# LED_individual_sign_Board1.net
KiCad netlist of a schematic drawn in EAGLE
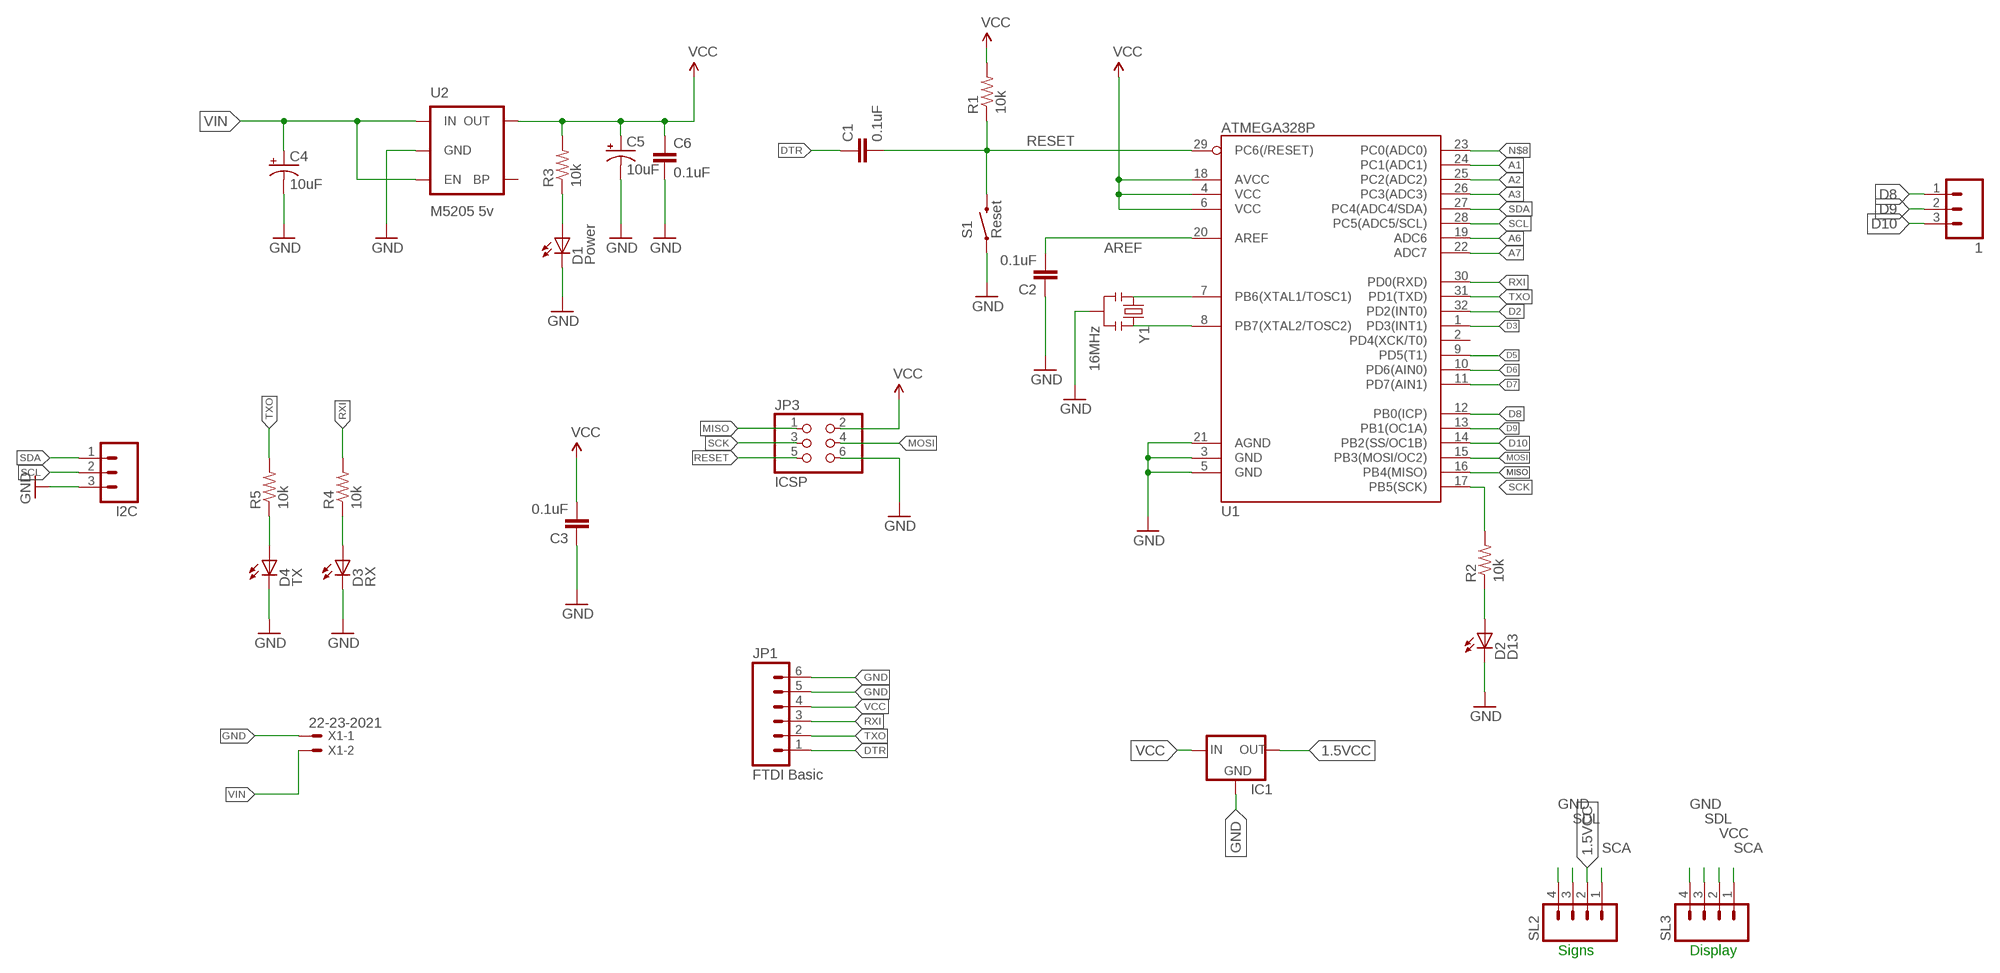
[diagram p0: schematic, sheet 1]

(export (version "E")
  (design (tool "Eeschema 10.0.6"))
  (components
    (comp (ref "1")
      (value "M03PTH")
      (footprint "eagle-import:1X03")
      (libsource (lib "eagle-import") (part "M03PTH"))
    )
    (comp (ref "C1")
      (value "0.1uF")
      (footprint "eagle-import:0603-CAP")
      (libsource (lib "eagle-import") (part "CAP0603-CAP"))
    )
    (comp (ref "C2")
      (value "0.1uF")
      (footprint "eagle-import:0603-CAP")
      (libsource (lib "eagle-import") (part "CAP0603-CAP"))
    )
    (comp (ref "C3")
      (value "0.1uF")
      (footprint "eagle-import:0603-CAP")
      (libsource (lib "eagle-import") (part "CAP0603-CAP"))
    )
    (comp (ref "C4")
      (value "10uF")
      (footprint "eagle-import:EIA3216")
      (libsource (lib "eagle-import") (part "CAP_POL1206"))
    )
    (comp (ref "C5")
      (value "10uF")
      (footprint "eagle-import:EIA3216")
      (libsource (lib "eagle-import") (part "CAP_POL1206"))
    )
    (comp (ref "C6")
      (value "0.1uF")
      (footprint "eagle-import:0603-CAP")
      (libsource (lib "eagle-import") (part "CAP0603-CAP"))
    )
    (comp (ref "D1")
      (value "Power")
      (footprint "eagle-import:LED-0603")
      (libsource (lib "eagle-import") (part "LED-RED0603"))
    )
    (comp (ref "D2")
      (value "D13")
      (footprint "eagle-import:LED-0603")
      (libsource (lib "eagle-import") (part "LED-RED0603"))
    )
    (comp (ref "D3")
      (value "RX")
      (footprint "eagle-import:LED-0603")
      (libsource (lib "eagle-import") (part "LED-GREEN0603"))
    )
    (comp (ref "D4")
      (value "TX")
      (footprint "eagle-import:LED-0603")
      (libsource (lib "eagle-import") (part "LED-RED0603"))
    )
    (comp (ref "I2C")
      (value "M03PTH")
      (footprint "eagle-import:1X03")
      (libsource (lib "eagle-import") (part "M03PTH"))
    )
    (comp (ref "IC1")
      (value "78XXS")
      (footprint "eagle-import:78XXS")
      (libsource (lib "eagle-import") (part "78XXS"))
    )
    (comp (ref "JP1")
      (value "FTDI Basic")
      (footprint "eagle-import:1X06")
      (libsource (lib "eagle-import") (part "M06SIP"))
    )
    (comp (ref "JP3")
      (value "ICSP")
      (footprint "eagle-import:2X03")
      (libsource (lib "eagle-import") (part "PINHD-2X3"))
    )
    (comp (ref "R1")
      (value "10k")
      (footprint "eagle-import:0603-RES")
      (libsource (lib "eagle-import") (part "RESISTOR0603-RES"))
    )
    (comp (ref "R2")
      (value "10k")
      (footprint "eagle-import:0603-RES")
      (libsource (lib "eagle-import") (part "RESISTOR0603-RES"))
    )
    (comp (ref "R3")
      (value "10k")
      (footprint "eagle-import:0603-RES")
      (libsource (lib "eagle-import") (part "RESISTOR0603-RES"))
    )
    (comp (ref "R4")
      (value "10k")
      (footprint "eagle-import:0603-RES")
      (libsource (lib "eagle-import") (part "RESISTOR0603-RES"))
    )
    (comp (ref "R5")
      (value "10k")
      (footprint "eagle-import:0603-RES")
      (libsource (lib "eagle-import") (part "RESISTOR0603-RES"))
    )
    (comp (ref "S1")
      (value "Reset")
      (footprint "eagle-import:TACTILE_SWITCH_SMD")
      (libsource (lib "eagle-import") (part "SWITCH-MOMENTARY-2SMD"))
    )
    (comp (ref "SL2")
      (value "M04")
      (footprint "eagle-import:04P")
      (libsource (lib "eagle-import") (part "M04"))
    )
    (comp (ref "SL3")
      (value "M04")
      (footprint "eagle-import:04P")
      (libsource (lib "eagle-import") (part "M04"))
    )
    (comp (ref "U1")
      (value "ATMEGA328P")
      (footprint "eagle-import:TQFP32-08")
      (libsource (lib "eagle-import") (part "ATMEGA328_SMT"))
    )
    (comp (ref "U2")
      (value "M5205 5v")
      (footprint "eagle-import:SOT23-5")
      (libsource (lib "eagle-import") (part "MIC52055V"))
    )
    (comp (ref "X1")
      (value "22-23-2021")
      (footprint "eagle-import:22-23-2021")
      (fields (field (name "MF") "MOLEX"))
      (libsource (lib "eagle-import") (part "22-23-2021"))
    )
    (comp (ref "Y1")
      (value "16MHz")
      (footprint "eagle-import:RESONATOR-SMD")
      (libsource (lib "eagle-import") (part "RESONATOR16MHZ"))
    )
  )
  (nets
    (net (code "1") (name "/AREF") (class "Default")
      (node (ref "C2") (pin "2") (pinfunction "2_2") (pintype "passive"))
      (node (ref "U1") (pin "20") (pinfunction "AREF_20") (pintype "bidirectional"))
    )
    (net (code "2") (name "/SCA") (class "Default")
      (node (ref "SL2") (pin "1") (pinfunction "1_1") (pintype "passive"))
      (node (ref "SL3") (pin "1") (pinfunction "1_1") (pintype "passive"))
    )
    (net (code "3") (name "/SDL") (class "Default")
      (node (ref "SL2") (pin "3") (pinfunction "3_3") (pintype "passive"))
      (node (ref "SL3") (pin "3") (pinfunction "3_3") (pintype "passive"))
    )
    (net (code "4") (name "1.5VCC") (class "Default")
      (node (ref "IC1") (pin "OUT") (pinfunction "OUT_OUT") (pintype "passive"))
      (node (ref "SL2") (pin "2") (pinfunction "2_2") (pintype "passive"))
    )
    (net (code "5") (name "A1") (class "Default")
      (node (ref "U1") (pin "24") (pinfunction "PC1(ADC1)_24") (pintype "bidirectional"))
    )
    (net (code "6") (name "A2") (class "Default")
      (node (ref "U1") (pin "25") (pinfunction "PC2(ADC2)_25") (pintype "bidirectional"))
    )
    (net (code "7") (name "A3") (class "Default")
      (node (ref "U1") (pin "26") (pinfunction "PC3(ADC3)_26") (pintype "bidirectional"))
    )
    (net (code "8") (name "A6") (class "Default")
      (node (ref "U1") (pin "19") (pinfunction "ADC6_19") (pintype "bidirectional"))
    )
    (net (code "9") (name "A7") (class "Default")
      (node (ref "U1") (pin "22") (pinfunction "ADC7_22") (pintype "bidirectional"))
    )
    (net (code "10") (name "D2") (class "Default")
      (node (ref "U1") (pin "32") (pinfunction "PD2(INT0)_32") (pintype "bidirectional"))
    )
    (net (code "11") (name "D3") (class "Default")
      (node (ref "U1") (pin "1") (pinfunction "PD3(INT1)_1") (pintype "bidirectional"))
    )
    (net (code "12") (name "D5") (class "Default")
      (node (ref "U1") (pin "9") (pinfunction "PD5(T1)_9") (pintype "bidirectional"))
    )
    (net (code "13") (name "D6") (class "Default")
      (node (ref "U1") (pin "10") (pinfunction "PD6(AIN0)_10") (pintype "bidirectional"))
    )
    (net (code "14") (name "D7") (class "Default")
      (node (ref "U1") (pin "11") (pinfunction "PD7(AIN1)_11") (pintype "bidirectional"))
    )
    (net (code "15") (name "D8") (class "Default")
      (node (ref "1") (pin "1") (pinfunction "1_1") (pintype "passive"))
      (node (ref "U1") (pin "12") (pinfunction "PB0(ICP)_12") (pintype "bidirectional"))
    )
    (net (code "16") (name "D9") (class "Default")
      (node (ref "1") (pin "2") (pinfunction "2_2") (pintype "passive"))
      (node (ref "U1") (pin "13") (pinfunction "PB1(OC1A)_13") (pintype "bidirectional"))
    )
    (net (code "17") (name "D10") (class "Default")
      (node (ref "1") (pin "3") (pinfunction "3_3") (pintype "passive"))
      (node (ref "U1") (pin "14") (pinfunction "PB2(SS/OC1B)_14") (pintype "bidirectional"))
    )
    (net (code "18") (name "DTR") (class "Default")
      (node (ref "C1") (pin "1") (pinfunction "1_1") (pintype "passive"))
      (node (ref "JP1") (pin "1") (pinfunction "1_1") (pintype "passive"))
    )
    (net (code "19") (name "GND") (class "Default")
      (node (ref "C2") (pin "1") (pinfunction "1_1") (pintype "passive"))
      (node (ref "C3") (pin "1") (pinfunction "1_1") (pintype "passive"))
      (node (ref "C4") (pin "C") (pinfunction "-_C") (pintype "passive"))
      (node (ref "C5") (pin "C") (pinfunction "-_C") (pintype "passive"))
      (node (ref "C6") (pin "2") (pinfunction "2_2") (pintype "passive"))
      (node (ref "D1") (pin "C") (pinfunction "C_C") (pintype "passive"))
      (node (ref "D2") (pin "C") (pinfunction "C_C") (pintype "passive"))
      (node (ref "D3") (pin "C") (pinfunction "C_C") (pintype "passive"))
      (node (ref "D4") (pin "C") (pinfunction "C_C") (pintype "passive"))
      (node (ref "I2C") (pin "3") (pinfunction "3_3") (pintype "passive"))
      (node (ref "IC1") (pin "GND") (pinfunction "GND_GND") (pintype "input"))
      (node (ref "JP1") (pin "5") (pinfunction "5_5") (pintype "passive"))
      (node (ref "JP1") (pin "6") (pinfunction "6_6") (pintype "passive"))
      (node (ref "JP3") (pin "6") (pinfunction "6_6") (pintype "passive"))
      (node (ref "S1") (pin "1") (pinfunction "1_1") (pintype "passive"))
      (node (ref "SL2") (pin "4") (pinfunction "4_4") (pintype "passive"))
      (node (ref "SL3") (pin "4") (pinfunction "4_4") (pintype "passive"))
      (node (ref "U1") (pin "21") (pinfunction "AGND_21") (pintype "bidirectional"))
      (node (ref "U1") (pin "3") (pinfunction "GND_3") (pintype "bidirectional"))
      (node (ref "U1") (pin "5") (pinfunction "GND_5") (pintype "bidirectional"))
      (node (ref "U2") (pin "2") (pinfunction "GND_2") (pintype "input"))
      (node (ref "X1") (pin "1") (pinfunction "S_1") (pintype "passive"))
      (node (ref "Y1") (pin "2") (pinfunction "2_2") (pintype "passive"))
    )
    (net (code "20") (name "MISO") (class "Default")
      (node (ref "JP3") (pin "1") (pinfunction "1_1") (pintype "passive"))
      (node (ref "U1") (pin "16") (pinfunction "PB4(MISO)_16") (pintype "bidirectional"))
    )
    (net (code "21") (name "MOSI") (class "Default")
      (node (ref "JP3") (pin "4") (pinfunction "4_4") (pintype "passive"))
      (node (ref "U1") (pin "15") (pinfunction "PB3(MOSI/OC2)_15") (pintype "bidirectional"))
    )
    (net (code "22") (name "N$8") (class "Default")
      (node (ref "U1") (pin "23") (pinfunction "PC0(ADC0)_23") (pintype "bidirectional"))
    )
    (net (code "23") (name "Net-(D1-PadA)") (class "Default")
      (node (ref "D1") (pin "A") (pinfunction "A_A") (pintype "passive"))
      (node (ref "R3") (pin "1") (pinfunction "1_1") (pintype "passive"))
    )
    (net (code "24") (name "Net-(D2-PadA)") (class "Default")
      (node (ref "D2") (pin "A") (pinfunction "A_A") (pintype "passive"))
      (node (ref "R2") (pin "1") (pinfunction "1_1") (pintype "passive"))
    )
    (net (code "25") (name "Net-(D3-PadA)") (class "Default")
      (node (ref "D3") (pin "A") (pinfunction "A_A") (pintype "passive"))
      (node (ref "R4") (pin "1") (pinfunction "1_1") (pintype "passive"))
    )
    (net (code "26") (name "Net-(D4-PadA)") (class "Default")
      (node (ref "D4") (pin "A") (pinfunction "A_A") (pintype "passive"))
      (node (ref "R5") (pin "1") (pinfunction "1_1") (pintype "passive"))
    )
    (net (code "27") (name "Net-(U1-PB6(XTAL1{slash}TOSC1))") (class "Default")
      (node (ref "U1") (pin "7") (pinfunction "PB6(XTAL1/TOSC1)_7") (pintype "bidirectional"))
      (node (ref "Y1") (pin "1") (pinfunction "1_1") (pintype "passive"))
    )
    (net (code "28") (name "Net-(U1-PB7(XTAL2{slash}TOSC2))") (class "Default")
      (node (ref "U1") (pin "8") (pinfunction "PB7(XTAL2/TOSC2)_8") (pintype "bidirectional"))
      (node (ref "Y1") (pin "3") (pinfunction "3_3") (pintype "passive"))
    )
    (net (code "29") (name "RESET") (class "Default")
      (node (ref "C1") (pin "2") (pinfunction "2_2") (pintype "passive"))
      (node (ref "JP3") (pin "5") (pinfunction "5_5") (pintype "passive"))
      (node (ref "R1") (pin "1") (pinfunction "1_1") (pintype "passive"))
      (node (ref "S1") (pin "3") (pinfunction "2_3") (pintype "passive"))
      (node (ref "U1") (pin "29") (pinfunction "PC6(/RESET)_29") (pintype "bidirectional"))
    )
    (net (code "30") (name "RXI") (class "Default")
      (node (ref "JP1") (pin "3") (pinfunction "3_3") (pintype "passive"))
      (node (ref "R4") (pin "2") (pinfunction "2_2") (pintype "passive"))
      (node (ref "U1") (pin "30") (pinfunction "PD0(RXD)_30") (pintype "bidirectional"))
    )
    (net (code "31") (name "SCK") (class "Default")
      (node (ref "JP3") (pin "3") (pinfunction "3_3") (pintype "passive"))
      (node (ref "R2") (pin "2") (pinfunction "2_2") (pintype "passive"))
      (node (ref "U1") (pin "17") (pinfunction "PB5(SCK)_17") (pintype "bidirectional"))
    )
    (net (code "32") (name "SCL") (class "Default")
      (node (ref "I2C") (pin "2") (pinfunction "2_2") (pintype "passive"))
      (node (ref "U1") (pin "28") (pinfunction "PC5(ADC5/SCL)_28") (pintype "bidirectional"))
    )
    (net (code "33") (name "SDA") (class "Default")
      (node (ref "I2C") (pin "1") (pinfunction "1_1") (pintype "passive"))
      (node (ref "U1") (pin "27") (pinfunction "PC4(ADC4/SDA)_27") (pintype "bidirectional"))
    )
    (net (code "34") (name "TXO") (class "Default")
      (node (ref "JP1") (pin "2") (pinfunction "2_2") (pintype "passive"))
      (node (ref "R5") (pin "2") (pinfunction "2_2") (pintype "passive"))
      (node (ref "U1") (pin "31") (pinfunction "PD1(TXD)_31") (pintype "bidirectional"))
    )
    (net (code "35") (name "VCC") (class "Default")
      (node (ref "C3") (pin "2") (pinfunction "2_2") (pintype "passive"))
      (node (ref "C5") (pin "A") (pinfunction "+_A") (pintype "passive"))
      (node (ref "C6") (pin "1") (pinfunction "1_1") (pintype "passive"))
      (node (ref "IC1") (pin "IN") (pinfunction "IN_IN") (pintype "input"))
      (node (ref "JP1") (pin "4") (pinfunction "4_4") (pintype "passive"))
      (node (ref "JP3") (pin "2") (pinfunction "2_2") (pintype "passive"))
      (node (ref "R1") (pin "2") (pinfunction "2_2") (pintype "passive"))
      (node (ref "R3") (pin "2") (pinfunction "2_2") (pintype "passive"))
      (node (ref "SL3") (pin "2") (pinfunction "2_2") (pintype "passive"))
      (node (ref "U1") (pin "18") (pinfunction "AVCC_18") (pintype "bidirectional"))
      (node (ref "U1") (pin "4") (pinfunction "VCC_4") (pintype "bidirectional"))
      (node (ref "U1") (pin "6") (pinfunction "VCC_6") (pintype "bidirectional"))
      (node (ref "U2") (pin "5") (pinfunction "OUT_5") (pintype "passive"))
    )
    (net (code "36") (name "VIN") (class "Default")
      (node (ref "C4") (pin "A") (pinfunction "+_A") (pintype "passive"))
      (node (ref "U2") (pin "1") (pinfunction "IN_1") (pintype "input"))
      (node (ref "U2") (pin "3") (pinfunction "EN_3") (pintype "input"))
      (node (ref "X1") (pin "2") (pinfunction "S_2") (pintype "passive"))
    )
    (net (code "37") (name "unconnected-(U1-PD4(XCK{slash}T0)-Pad2)") (class "Default")
      (node (ref "U1") (pin "2") (pinfunction "PD4(XCK/T0)_2") (pintype "bidirectional"))
    )
    (net (code "38") (name "unconnected-(U2-BP-Pad4)") (class "Default")
      (node (ref "U2") (pin "4") (pinfunction "BP_4") (pintype "input"))
    )
  )
)
